# NixieClock_68k.net
KiCad netlist of a schematic drawn in EAGLE
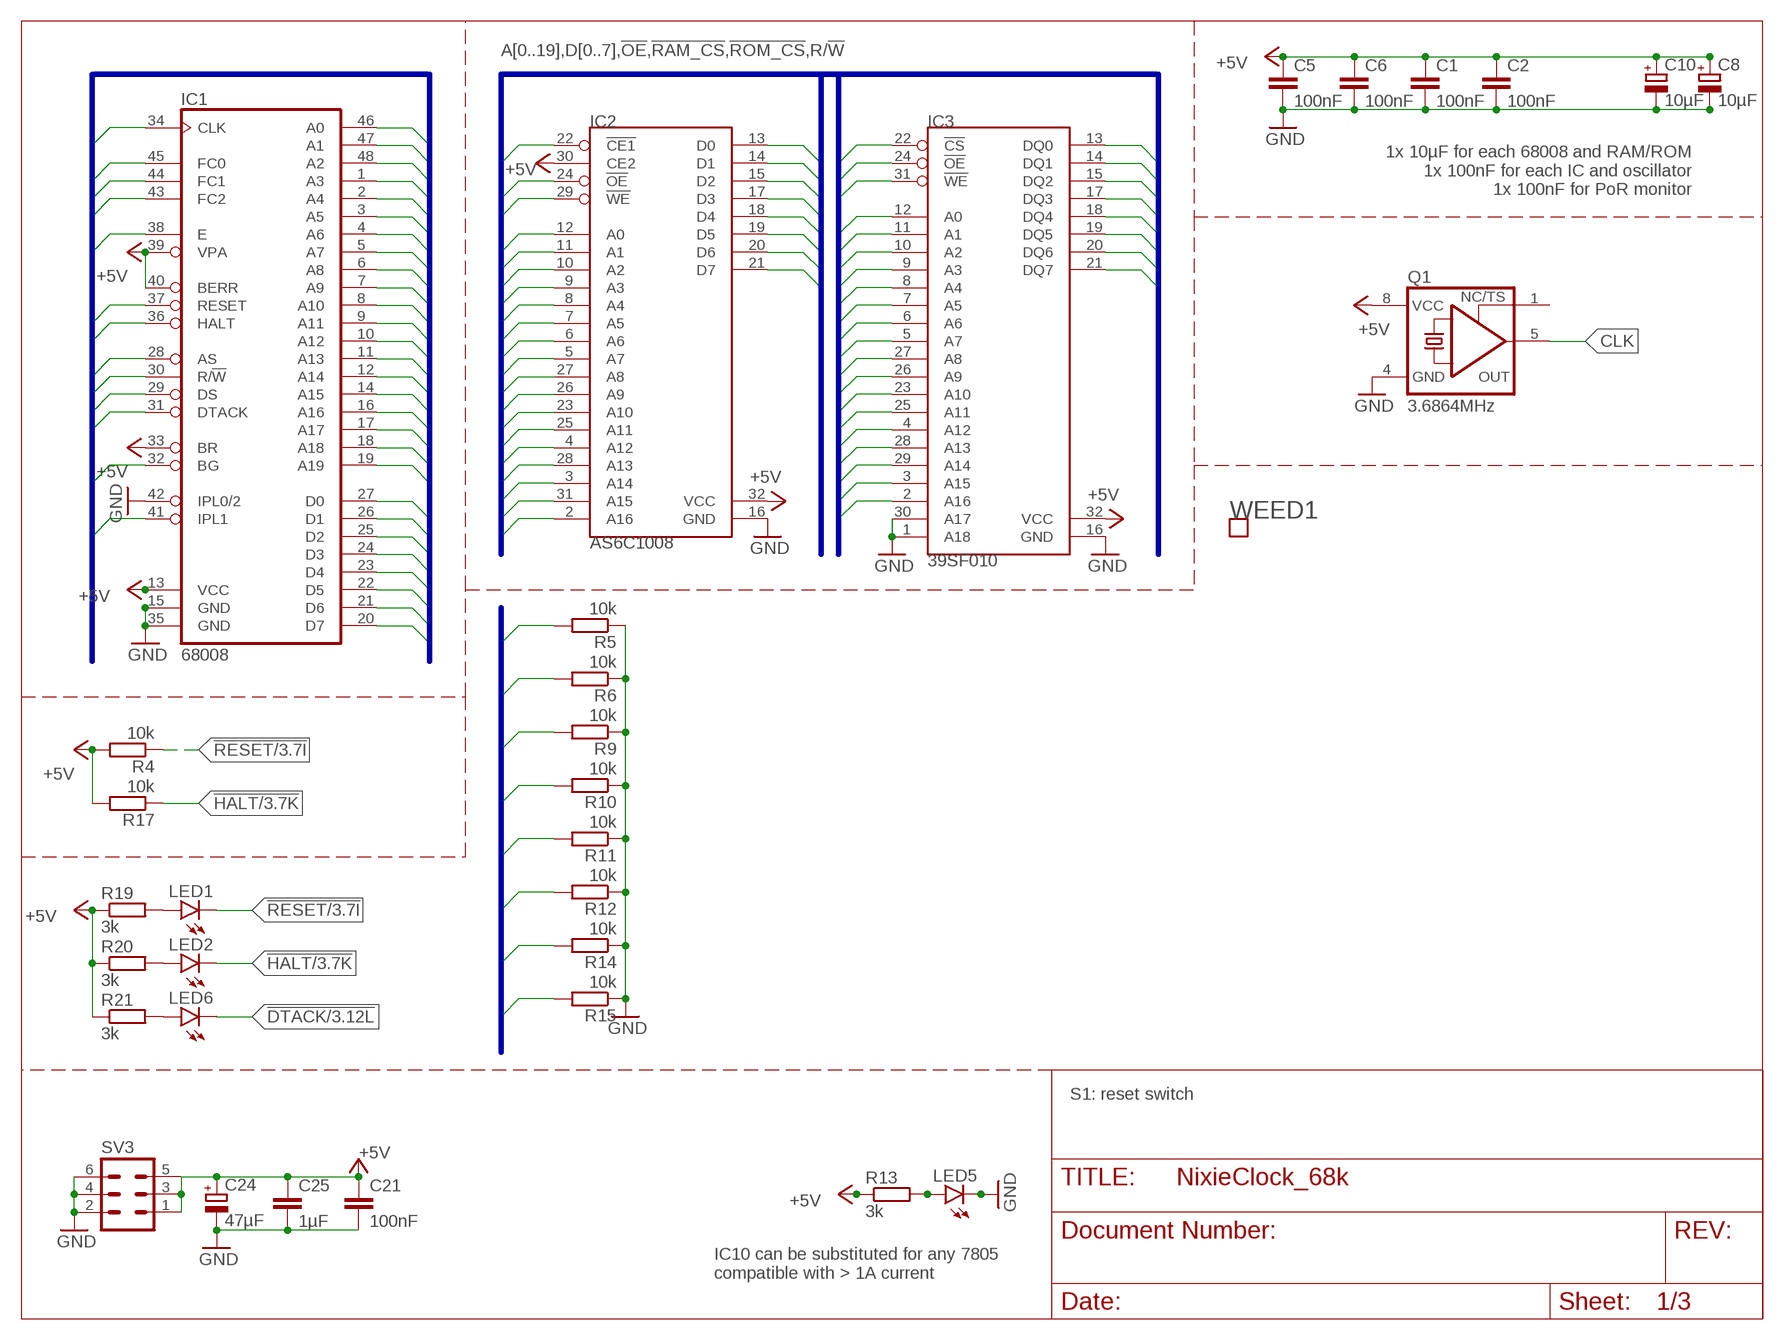
[diagram p0: schematic, sheet 1]
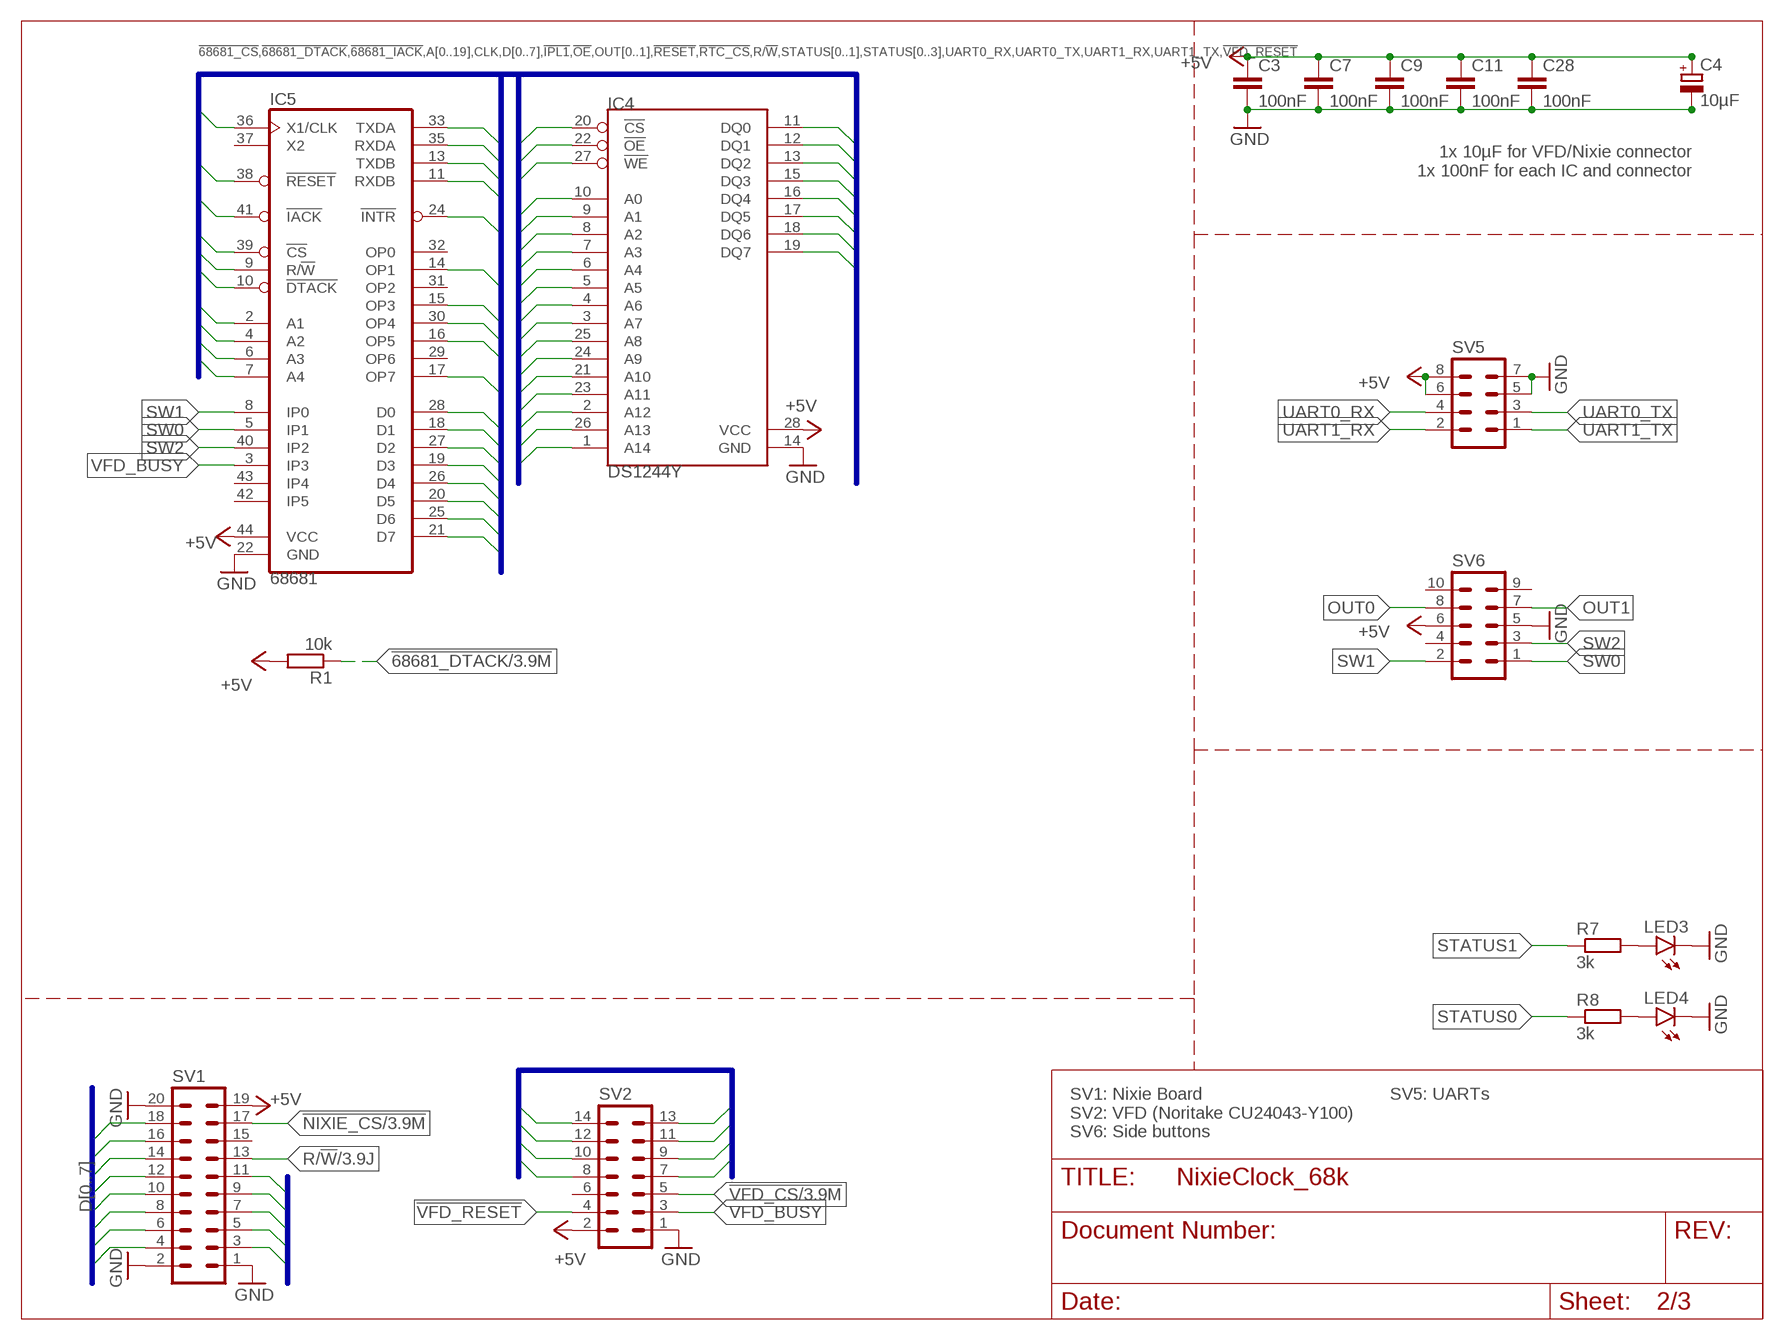
[diagram p1: schematic, sheet 2]
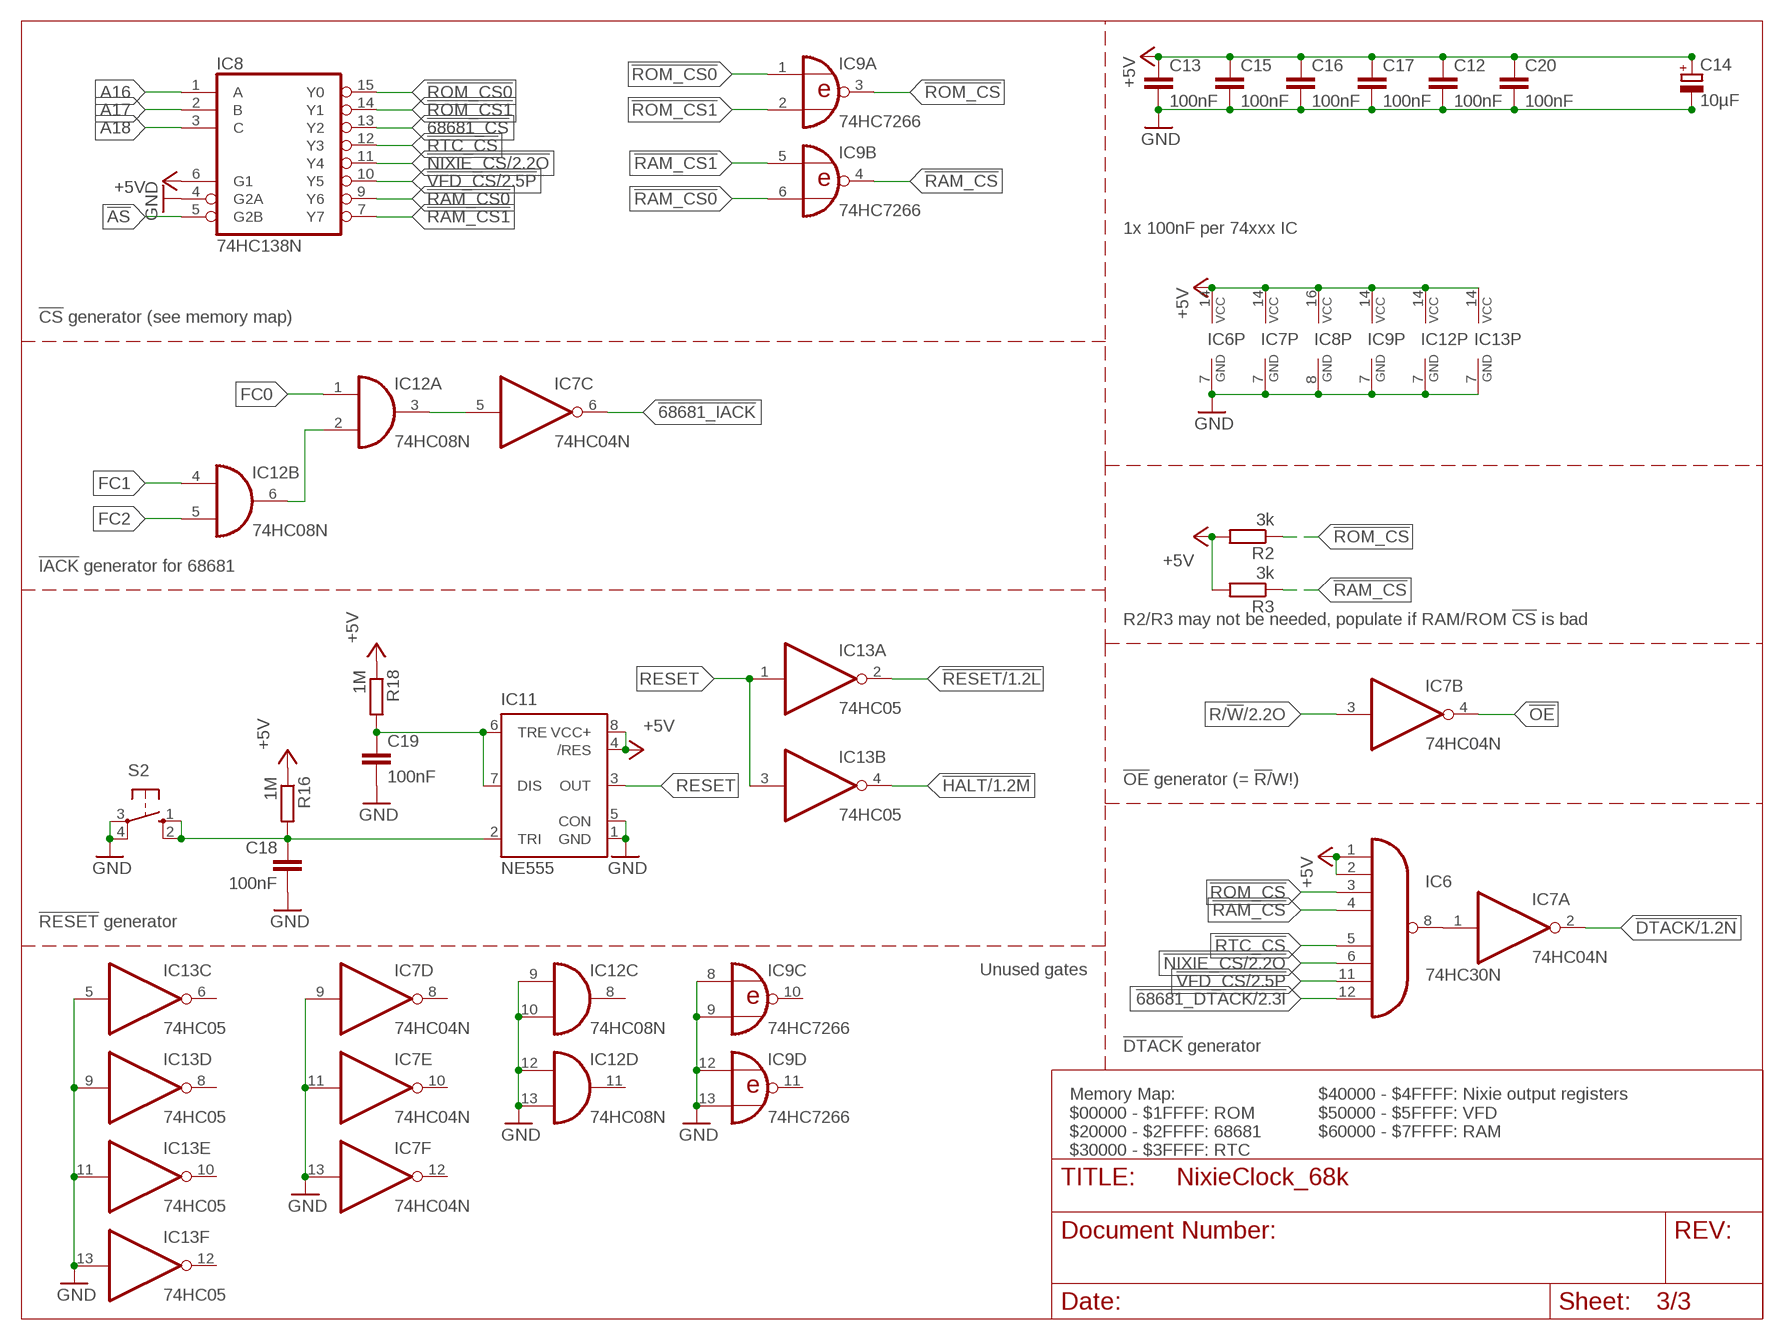
[diagram p2: schematic, sheet 3]

(export (version "E")
  (design (tool "Eeschema 10.0.6"))
  (components
    (comp (ref "C12")
      (value "100nF")
      (footprint "eagle-import:C0805")
      (libsource (lib "eagle-import") (part "C-EUC0805"))
    )
    (comp (ref "C13")
      (value "100nF")
      (footprint "eagle-import:C0805")
      (libsource (lib "eagle-import") (part "C-EUC0805"))
    )
    (comp (ref "C14")
      (value "10µF")
      (footprint "eagle-import:SMC_B")
      (libsource (lib "eagle-import") (part "CPOL-EUSMCB"))
    )
    (comp (ref "C15")
      (value "100nF")
      (footprint "eagle-import:C0805")
      (libsource (lib "eagle-import") (part "C-EUC0805"))
    )
    (comp (ref "C16")
      (value "100nF")
      (footprint "eagle-import:C0805")
      (libsource (lib "eagle-import") (part "C-EUC0805"))
    )
    (comp (ref "C17")
      (value "100nF")
      (footprint "eagle-import:C0805")
      (libsource (lib "eagle-import") (part "C-EUC0805"))
    )
    (comp (ref "C18")
      (value "100nF")
      (footprint "eagle-import:C0805")
      (libsource (lib "eagle-import") (part "C-EUC0805"))
    )
    (comp (ref "C19")
      (value "100nF")
      (footprint "eagle-import:C0805")
      (libsource (lib "eagle-import") (part "C-EUC0805"))
    )
    (comp (ref "C20")
      (value "100nF")
      (footprint "eagle-import:C0805")
      (libsource (lib "eagle-import") (part "C-EUC0805"))
    )
    (comp (ref "IC6")
      (value "74HC30N")
      (footprint "eagle-import:DIL14")
      (fields (field (name "MOUSER") "595-CD74HC30E"))
      (libsource (lib "eagle-import") (part "7430NHC"))
    )
    (comp (ref "IC7")
      (value "74HC04N")
      (footprint "eagle-import:DIL14")
      (fields (field (name "MOUSER") "595-SN74HC04AN"))
      (libsource (lib "eagle-import") (part "7404NHC"))
    )
    (comp (ref "IC8")
      (value "74HC138N")
      (footprint "eagle-import:DIL16")
      (fields (field (name "MOUSER") "595-SN74HC138N"))
      (libsource (lib "eagle-import") (part "74138NHC"))
    )
    (comp (ref "IC9")
      (value "74HC7266")
      (footprint "eagle-import:DIL14")
      (fields (field (name "MOUSER") "595-CD74HC7266E"))
      (libsource (lib "eagle-import") (part "74266NHC"))
    )
    (comp (ref "IC11")
      (value "NE555")
      (footprint "eagle-import:DIL-08")
      (fields (field (name "MF") "Arrow Electronics") (field (name "MPN") "NE555N"))
      (libsource (lib "eagle-import") (part "NE555"))
    )
    (comp (ref "IC12")
      (value "74HC08N")
      (footprint "eagle-import:DIL14")
      (fields (field (name "MOUSER") "595-SN74HC08AN"))
      (libsource (lib "eagle-import") (part "7408NHC"))
    )
    (comp (ref "IC13")
      (value "74HC05")
      (footprint "eagle-import:DIL14")
      (fields (field (name "MOUSER") "595-SN74HC05N"))
      (libsource (lib "eagle-import") (part "7405NHCT"))
    )
    (comp (ref "R2")
      (value "3k")
      (footprint "eagle-import:R2012")
      (libsource (lib "eagle-import") (part "R-EU_R2012"))
    )
    (comp (ref "R3")
      (value "3k")
      (footprint "eagle-import:R2012")
      (libsource (lib "eagle-import") (part "R-EU_R2012"))
    )
    (comp (ref "R16")
      (value "1M")
      (footprint "eagle-import:R2012")
      (libsource (lib "eagle-import") (part "R-EU_R2012"))
    )
    (comp (ref "R18")
      (value "1M")
      (footprint "eagle-import:R2012")
      (libsource (lib "eagle-import") (part "R-EU_R2012"))
    )
    (comp (ref "S2")
      (value "10-XX")
      (footprint "eagle-import:B3F-10XX")
      (fields (field (name "MPN") "B3F-1000"))
      (libsource (lib "eagle-import") (part "10-XX"))
    )
    (comp (ref "C3")
      (value "100nF")
      (footprint "eagle-import:C0805")
      (libsource (lib "eagle-import") (part "C-EUC0805"))
    )
    (comp (ref "C4")
      (value "10µF")
      (footprint "eagle-import:SMC_B")
      (libsource (lib "eagle-import") (part "CPOL-EUSMCB"))
    )
    (comp (ref "C7")
      (value "100nF")
      (footprint "eagle-import:C0805")
      (libsource (lib "eagle-import") (part "C-EUC0805"))
    )
    (comp (ref "C9")
      (value "100nF")
      (footprint "eagle-import:C0805")
      (libsource (lib "eagle-import") (part "C-EUC0805"))
    )
    (comp (ref "C11")
      (value "100nF")
      (footprint "eagle-import:C0805")
      (libsource (lib "eagle-import") (part "C-EUC0805"))
    )
    (comp (ref "C28")
      (value "100nF")
      (footprint "eagle-import:C0805")
      (libsource (lib "eagle-import") (part "C-EUC0805"))
    )
    (comp (ref "IC4")
      (value "DS1244Y")
      (footprint "eagle-import:DIL28-6")
      (libsource (lib "eagle-import") (part "DS1244EDIP-28"))
    )
    (comp (ref "IC5")
      (value "68681")
      (footprint "eagle-import:PLCC-S44")
      (libsource (lib "eagle-import") (part "MC68681PLCC44-SOCKET"))
    )
    (comp (ref "LED3")
      (value "LEDCHIPLED_1206")
      (footprint "eagle-import:CHIPLED_1206")
      (libsource (lib "eagle-import") (part "LEDCHIPLED_1206"))
    )
    (comp (ref "LED4")
      (value "LEDCHIPLED_1206")
      (footprint "eagle-import:CHIPLED_1206")
      (libsource (lib "eagle-import") (part "LEDCHIPLED_1206"))
    )
    (comp (ref "R1")
      (value "10k")
      (footprint "eagle-import:R2012")
      (libsource (lib "eagle-import") (part "R-EU_R2012"))
    )
    (comp (ref "R7")
      (value "3k")
      (footprint "eagle-import:R2012")
      (libsource (lib "eagle-import") (part "R-EU_R2012"))
    )
    (comp (ref "R8")
      (value "3k")
      (footprint "eagle-import:R2012")
      (libsource (lib "eagle-import") (part "R-EU_R2012"))
    )
    (comp (ref "SV1")
      (value "MA10-2")
      (footprint "eagle-import:MA10-2")
      (libsource (lib "eagle-import") (part "MA10-2"))
    )
    (comp (ref "SV2")
      (value "MA07-2")
      (footprint "eagle-import:MA07-2")
      (libsource (lib "eagle-import") (part "MA07-2"))
    )
    (comp (ref "SV5")
      (value "MA04-2")
      (footprint "eagle-import:MA04-2")
      (libsource (lib "eagle-import") (part "MA04-2"))
    )
    (comp (ref "SV6")
      (value "MA05-2")
      (footprint "eagle-import:MA05-2")
      (libsource (lib "eagle-import") (part "MA05-2"))
    )
    (comp (ref "C1")
      (value "100nF")
      (footprint "eagle-import:C0805")
      (libsource (lib "eagle-import") (part "C-EUC0805"))
    )
    (comp (ref "C2")
      (value "100nF")
      (footprint "eagle-import:C0805")
      (libsource (lib "eagle-import") (part "C-EUC0805"))
    )
    (comp (ref "C5")
      (value "100nF")
      (footprint "eagle-import:C0805")
      (libsource (lib "eagle-import") (part "C-EUC0805"))
    )
    (comp (ref "C6")
      (value "100nF")
      (footprint "eagle-import:C0805")
      (libsource (lib "eagle-import") (part "C-EUC0805"))
    )
    (comp (ref "C8")
      (value "10µF")
      (footprint "eagle-import:SMC_B")
      (libsource (lib "eagle-import") (part "CPOL-EUSMCB"))
    )
    (comp (ref "C10")
      (value "10µF")
      (footprint "eagle-import:SMC_B")
      (libsource (lib "eagle-import") (part "CPOL-EUSMCB"))
    )
    (comp (ref "C21")
      (value "100nF")
      (footprint "eagle-import:C0805")
      (libsource (lib "eagle-import") (part "C-EUC0805"))
    )
    (comp (ref "C24")
      (value "47µF")
      (footprint "eagle-import:CT6032")
      (libsource (lib "eagle-import") (part "CPOL-EUCT6032"))
    )
    (comp (ref "C25")
      (value "1µF")
      (footprint "eagle-import:C0805")
      (libsource (lib "eagle-import") (part "C-EUC0805"))
    )
    (comp (ref "IC1")
      (value "68008")
      (footprint "eagle-import:DIL48")
      (libsource (lib "eagle-import") (part "MC68008P"))
    )
    (comp (ref "IC2")
      (value "AS6C1008")
      (footprint "eagle-import:DIL32")
      (libsource (lib "eagle-import") (part "AS6C1008"))
    )
    (comp (ref "IC3")
      (value "39SF010")
      (footprint "eagle-import:DIL32")
      (fields (field (name "MOUSER") "804-39SF010A7CPHE"))
      (libsource (lib "eagle-import") (part "SST39SF0X0PDIP32"))
    )
    (comp (ref "LED1")
      (value "LEDCHIPLED_1206")
      (footprint "eagle-import:CHIPLED_1206")
      (libsource (lib "eagle-import") (part "LEDCHIPLED_1206"))
    )
    (comp (ref "LED2")
      (value "LEDCHIPLED_1206")
      (footprint "eagle-import:CHIPLED_1206")
      (libsource (lib "eagle-import") (part "LEDCHIPLED_1206"))
    )
    (comp (ref "LED5")
      (value "LEDCHIPLED_1206")
      (footprint "eagle-import:CHIPLED_1206")
      (libsource (lib "eagle-import") (part "LEDCHIPLED_1206"))
    )
    (comp (ref "LED6")
      (value "LEDCHIPLED_1206")
      (footprint "eagle-import:CHIPLED_1206")
      (libsource (lib "eagle-import") (part "LEDCHIPLED_1206"))
    )
    (comp (ref "Q1")
      (value "3.6864MHz")
      (footprint "eagle-import:DIL08S")
      (libsource (lib "eagle-import") (part "XO-8"))
    )
    (comp (ref "R4")
      (value "10k")
      (footprint "eagle-import:R2012")
      (libsource (lib "eagle-import") (part "R-EU_R2012"))
    )
    (comp (ref "R5")
      (value "10k")
      (footprint "eagle-import:R2012")
      (libsource (lib "eagle-import") (part "R-EU_R2012"))
    )
    (comp (ref "R6")
      (value "10k")
      (footprint "eagle-import:R2012")
      (libsource (lib "eagle-import") (part "R-EU_R2012"))
    )
    (comp (ref "R9")
      (value "10k")
      (footprint "eagle-import:R2012")
      (libsource (lib "eagle-import") (part "R-EU_R2012"))
    )
    (comp (ref "R10")
      (value "10k")
      (footprint "eagle-import:R2012")
      (libsource (lib "eagle-import") (part "R-EU_R2012"))
    )
    (comp (ref "R11")
      (value "10k")
      (footprint "eagle-import:R2012")
      (libsource (lib "eagle-import") (part "R-EU_R2012"))
    )
    (comp (ref "R12")
      (value "10k")
      (footprint "eagle-import:R2012")
      (libsource (lib "eagle-import") (part "R-EU_R2012"))
    )
    (comp (ref "R13")
      (value "3k")
      (footprint "eagle-import:R2012")
      (libsource (lib "eagle-import") (part "R-EU_R2012"))
    )
    (comp (ref "R14")
      (value "10k")
      (footprint "eagle-import:R2012")
      (libsource (lib "eagle-import") (part "R-EU_R2012"))
    )
    (comp (ref "R15")
      (value "10k")
      (footprint "eagle-import:R2012")
      (libsource (lib "eagle-import") (part "R-EU_R2012"))
    )
    (comp (ref "R17")
      (value "10k")
      (footprint "eagle-import:R2012")
      (libsource (lib "eagle-import") (part "R-EU_R2012"))
    )
    (comp (ref "R19")
      (value "3k")
      (footprint "eagle-import:R2012")
      (libsource (lib "eagle-import") (part "R-EU_R2012"))
    )
    (comp (ref "R20")
      (value "3k")
      (footprint "eagle-import:R2012")
      (libsource (lib "eagle-import") (part "R-EU_R2012"))
    )
    (comp (ref "R21")
      (value "3k")
      (footprint "eagle-import:R2012")
      (libsource (lib "eagle-import") (part "R-EU_R2012"))
    )
    (comp (ref "SV3")
      (value "MA03-2")
      (footprint "eagle-import:MA03-2")
      (libsource (lib "eagle-import") (part "MA03-2"))
    )
    (comp (ref "WEED1")
      (value "WEED")
      (footprint "eagle-import:DOINK")
      (libsource (lib "eagle-import") (part "WEED"))
    )
  )
  (nets
    (net (code "1") (name "+5V") (class "Default")
      (node (ref "C1") (pin "1") (pinfunction "1_1") (pintype "passive"))
      (node (ref "C10") (pin "+") (pinfunction "+_+") (pintype "passive"))
      (node (ref "C11") (pin "1") (pinfunction "1_1") (pintype "passive"))
      (node (ref "C12") (pin "1") (pinfunction "1_1") (pintype "passive"))
      (node (ref "C13") (pin "1") (pinfunction "1_1") (pintype "passive"))
      (node (ref "C14") (pin "+") (pinfunction "+_+") (pintype "passive"))
      (node (ref "C15") (pin "1") (pinfunction "1_1") (pintype "passive"))
      (node (ref "C16") (pin "1") (pinfunction "1_1") (pintype "passive"))
      (node (ref "C17") (pin "1") (pinfunction "1_1") (pintype "passive"))
      (node (ref "C2") (pin "1") (pinfunction "1_1") (pintype "passive"))
      (node (ref "C20") (pin "1") (pinfunction "1_1") (pintype "passive"))
      (node (ref "C21") (pin "1") (pinfunction "1_1") (pintype "passive"))
      (node (ref "C24") (pin "+") (pinfunction "+_+") (pintype "passive"))
      (node (ref "C25") (pin "1") (pinfunction "1_1") (pintype "passive"))
      (node (ref "C28") (pin "1") (pinfunction "1_1") (pintype "passive"))
      (node (ref "C3") (pin "1") (pinfunction "1_1") (pintype "passive"))
      (node (ref "C4") (pin "+") (pinfunction "+_+") (pintype "passive"))
      (node (ref "C5") (pin "1") (pinfunction "1_1") (pintype "passive"))
      (node (ref "C6") (pin "1") (pinfunction "1_1") (pintype "passive"))
      (node (ref "C7") (pin "1") (pinfunction "1_1") (pintype "passive"))
      (node (ref "C8") (pin "+") (pinfunction "+_+") (pintype "passive"))
      (node (ref "C9") (pin "1") (pinfunction "1_1") (pintype "passive"))
      (node (ref "IC1") (pin "13") (pinfunction "VCC_13") (pintype "power_in"))
      (node (ref "IC1") (pin "33") (pinfunction "BR_33") (pintype "input"))
      (node (ref "IC1") (pin "39") (pinfunction "VPA_39") (pintype "input"))
      (node (ref "IC1") (pin "40") (pinfunction "BERR_40") (pintype "input"))
      (node (ref "IC11") (pin "4") (pinfunction "/RES_4") (pintype "input"))
      (node (ref "IC11") (pin "8") (pinfunction "VCC+_8") (pintype "power_in"))
      (node (ref "IC12") (pin "14") (pinfunction "VCC_14") (pintype "power_in"))
      (node (ref "IC13") (pin "14") (pinfunction "VCC_14") (pintype "power_in"))
      (node (ref "IC2") (pin "30") (pinfunction "CE2_30") (pintype "input"))
      (node (ref "IC2") (pin "32") (pinfunction "VCC_32") (pintype "power_in"))
      (node (ref "IC3") (pin "32") (pinfunction "VCC_32") (pintype "power_in"))
      (node (ref "IC4") (pin "28") (pinfunction "VCC_28") (pintype "power_in"))
      (node (ref "IC5") (pin "44") (pinfunction "VCC_44") (pintype "power_in"))
      (node (ref "IC6") (pin "1") (pinfunction "I0_1") (pintype "input"))
      (node (ref "IC6") (pin "14") (pinfunction "VCC_14") (pintype "power_in"))
      (node (ref "IC6") (pin "2") (pinfunction "I1_2") (pintype "input"))
      (node (ref "IC7") (pin "14") (pinfunction "VCC_14") (pintype "power_in"))
      (node (ref "IC8") (pin "16") (pinfunction "VCC_16") (pintype "power_in"))
      (node (ref "IC8") (pin "6") (pinfunction "G1_6") (pintype "input"))
      (node (ref "IC9") (pin "14") (pinfunction "VCC_14") (pintype "power_in"))
      (node (ref "Q1") (pin "8") (pinfunction "VCC_8") (pintype "power_in"))
      (node (ref "R1") (pin "2") (pinfunction "2_2") (pintype "passive"))
      (node (ref "R13") (pin "1") (pinfunction "1_1") (pintype "passive"))
      (node (ref "R16") (pin "1") (pinfunction "1_1") (pintype "passive"))
      (node (ref "R17") (pin "2") (pinfunction "2_2") (pintype "passive"))
      (node (ref "R18") (pin "1") (pinfunction "1_1") (pintype "passive"))
      (node (ref "R19") (pin "1") (pinfunction "1_1") (pintype "passive"))
      (node (ref "R2") (pin "2") (pinfunction "2_2") (pintype "passive"))
      (node (ref "R20") (pin "1") (pinfunction "1_1") (pintype "passive"))
      (node (ref "R21") (pin "1") (pinfunction "1_1") (pintype "passive"))
      (node (ref "R3") (pin "2") (pinfunction "2_2") (pintype "passive"))
      (node (ref "R4") (pin "2") (pinfunction "2_2") (pintype "passive"))
      (node (ref "SV1") (pin "19") (pinfunction "19_19") (pintype "passive"))
      (node (ref "SV2") (pin "2") (pinfunction "2_2") (pintype "passive"))
      (node (ref "SV3") (pin "1") (pinfunction "1_1") (pintype "passive"))
      (node (ref "SV3") (pin "3") (pinfunction "3_3") (pintype "passive"))
      (node (ref "SV3") (pin "5") (pinfunction "5_5") (pintype "passive"))
      (node (ref "SV5") (pin "6") (pinfunction "6_6") (pintype "passive"))
      (node (ref "SV5") (pin "8") (pinfunction "8_8") (pintype "passive"))
      (node (ref "SV6") (pin "6") (pinfunction "6_6") (pintype "passive"))
    )
    (net (code "5") (name "A0") (class "Default")
      (node (ref "IC1") (pin "46") (pinfunction "A0_46") (pintype "output"))
      (node (ref "IC2") (pin "12") (pinfunction "A0_12") (pintype "input"))
      (node (ref "IC3") (pin "12") (pinfunction "A0_12") (pintype "input"))
      (node (ref "IC4") (pin "10") (pinfunction "A0_10") (pintype "input"))
      (node (ref "IC5") (pin "2") (pinfunction "A1_2") (pintype "input"))
      (node (ref "SV1") (pin "3") (pinfunction "3_3") (pintype "passive"))
    )
    (net (code "6") (name "A1") (class "Default")
      (node (ref "IC1") (pin "47") (pinfunction "A1_47") (pintype "output"))
      (node (ref "IC2") (pin "11") (pinfunction "A1_11") (pintype "input"))
      (node (ref "IC3") (pin "11") (pinfunction "A1_11") (pintype "input"))
      (node (ref "IC4") (pin "9") (pinfunction "A1_9") (pintype "input"))
      (node (ref "IC5") (pin "4") (pinfunction "A2_4") (pintype "input"))
      (node (ref "SV1") (pin "5") (pinfunction "5_5") (pintype "passive"))
    )
    (net (code "7") (name "A2") (class "Default")
      (node (ref "IC1") (pin "48") (pinfunction "A2_48") (pintype "output"))
      (node (ref "IC2") (pin "10") (pinfunction "A2_10") (pintype "input"))
      (node (ref "IC3") (pin "10") (pinfunction "A2_10") (pintype "input"))
      (node (ref "IC4") (pin "8") (pinfunction "A2_8") (pintype "input"))
      (node (ref "IC5") (pin "6") (pinfunction "A3_6") (pintype "input"))
      (node (ref "SV1") (pin "7") (pinfunction "7_7") (pintype "passive"))
    )
    (net (code "8") (name "A3") (class "Default")
      (node (ref "IC1") (pin "1") (pinfunction "A3_1") (pintype "output"))
      (node (ref "IC2") (pin "9") (pinfunction "A3_9") (pintype "input"))
      (node (ref "IC3") (pin "9") (pinfunction "A3_9") (pintype "input"))
      (node (ref "IC4") (pin "7") (pinfunction "A3_7") (pintype "input"))
      (node (ref "IC5") (pin "7") (pinfunction "A4_7") (pintype "input"))
      (node (ref "SV1") (pin "9") (pinfunction "9_9") (pintype "passive"))
    )
    (net (code "9") (name "A4") (class "Default")
      (node (ref "IC1") (pin "2") (pinfunction "A4_2") (pintype "output"))
      (node (ref "IC2") (pin "8") (pinfunction "A4_8") (pintype "input"))
      (node (ref "IC3") (pin "8") (pinfunction "A4_8") (pintype "input"))
      (node (ref "IC4") (pin "6") (pinfunction "A4_6") (pintype "input"))
      (node (ref "SV1") (pin "11") (pinfunction "11_11") (pintype "passive"))
    )
    (net (code "10") (name "A5") (class "Default")
      (node (ref "IC1") (pin "3") (pinfunction "A5_3") (pintype "output"))
      (node (ref "IC2") (pin "7") (pinfunction "A5_7") (pintype "input"))
      (node (ref "IC3") (pin "7") (pinfunction "A5_7") (pintype "input"))
      (node (ref "IC4") (pin "5") (pinfunction "A5_5") (pintype "input"))
    )
    (net (code "11") (name "A6") (class "Default")
      (node (ref "IC1") (pin "4") (pinfunction "A6_4") (pintype "output"))
      (node (ref "IC2") (pin "6") (pinfunction "A6_6") (pintype "input"))
      (node (ref "IC3") (pin "6") (pinfunction "A6_6") (pintype "input"))
      (node (ref "IC4") (pin "4") (pinfunction "A6_4") (pintype "input"))
    )
    (net (code "12") (name "A7") (class "Default")
      (node (ref "IC1") (pin "5") (pinfunction "A7_5") (pintype "output"))
      (node (ref "IC2") (pin "5") (pinfunction "A7_5") (pintype "input"))
      (node (ref "IC3") (pin "5") (pinfunction "A7_5") (pintype "input"))
      (node (ref "IC4") (pin "3") (pinfunction "A7_3") (pintype "input"))
    )
    (net (code "13") (name "A8") (class "Default")
      (node (ref "IC1") (pin "6") (pinfunction "A8_6") (pintype "output"))
      (node (ref "IC2") (pin "27") (pinfunction "A8_27") (pintype "input"))
      (node (ref "IC3") (pin "27") (pinfunction "A8_27") (pintype "input"))
      (node (ref "IC4") (pin "25") (pinfunction "A8_25") (pintype "input"))
    )
    (net (code "14") (name "A9") (class "Default")
      (node (ref "IC1") (pin "7") (pinfunction "A9_7") (pintype "output"))
      (node (ref "IC2") (pin "26") (pinfunction "A9_26") (pintype "input"))
      (node (ref "IC3") (pin "26") (pinfunction "A9_26") (pintype "input"))
      (node (ref "IC4") (pin "24") (pinfunction "A9_24") (pintype "input"))
    )
    (net (code "15") (name "A10") (class "Default")
      (node (ref "IC1") (pin "8") (pinfunction "A10_8") (pintype "output"))
      (node (ref "IC2") (pin "23") (pinfunction "A10_23") (pintype "input"))
      (node (ref "IC3") (pin "23") (pinfunction "A10_23") (pintype "input"))
      (node (ref "IC4") (pin "21") (pinfunction "A10_21") (pintype "input"))
    )
    (net (code "16") (name "A11") (class "Default")
      (node (ref "IC1") (pin "9") (pinfunction "A11_9") (pintype "output"))
      (node (ref "IC2") (pin "25") (pinfunction "A11_25") (pintype "input"))
      (node (ref "IC3") (pin "25") (pinfunction "A11_25") (pintype "input"))
      (node (ref "IC4") (pin "23") (pinfunction "A11_23") (pintype "input"))
    )
    (net (code "17") (name "A12") (class "Default")
      (node (ref "IC1") (pin "10") (pinfunction "A12_10") (pintype "output"))
      (node (ref "IC2") (pin "4") (pinfunction "A12_4") (pintype "input"))
      (node (ref "IC3") (pin "4") (pinfunction "A12_4") (pintype "input"))
      (node (ref "IC4") (pin "2") (pinfunction "A12_2") (pintype "input"))
    )
    (net (code "18") (name "A13") (class "Default")
      (node (ref "IC1") (pin "11") (pinfunction "A13_11") (pintype "output"))
      (node (ref "IC2") (pin "28") (pinfunction "A13_28") (pintype "input"))
      (node (ref "IC3") (pin "28") (pinfunction "A13_28") (pintype "input"))
      (node (ref "IC4") (pin "26") (pinfunction "A13_26") (pintype "input"))
    )
    (net (code "19") (name "A14") (class "Default")
      (node (ref "IC1") (pin "12") (pinfunction "A14_12") (pintype "output"))
      (node (ref "IC2") (pin "3") (pinfunction "A14_3") (pintype "input"))
      (node (ref "IC3") (pin "29") (pinfunction "A14_29") (pintype "input"))
      (node (ref "IC4") (pin "1") (pinfunction "A14_1") (pintype "input"))
    )
    (net (code "20") (name "A15") (class "Default")
      (node (ref "IC1") (pin "14") (pinfunction "A15_14") (pintype "output"))
      (node (ref "IC2") (pin "31") (pinfunction "A15_31") (pintype "input"))
      (node (ref "IC3") (pin "3") (pinfunction "A15_3") (pintype "input"))
    )
    (net (code "21") (name "A16") (class "Default")
      (node (ref "IC1") (pin "16") (pinfunction "A16_16") (pintype "output"))
      (node (ref "IC2") (pin "2") (pinfunction "A16_2") (pintype "input"))
      (node (ref "IC3") (pin "2") (pinfunction "A16_2") (pintype "input"))
      (node (ref "IC8") (pin "1") (pinfunction "A_1") (pintype "input"))
    )
    (net (code "22") (name "A17") (class "Default")
      (node (ref "IC1") (pin "17") (pinfunction "A17_17") (pintype "output"))
      (node (ref "IC8") (pin "2") (pinfunction "B_2") (pintype "input"))
    )
    (net (code "23") (name "A18") (class "Default")
      (node (ref "IC1") (pin "18") (pinfunction "A18_18") (pintype "output"))
      (node (ref "IC8") (pin "3") (pinfunction "C_3") (pintype "input"))
    )
    (net (code "24") (name "CLK") (class "Default")
      (node (ref "IC1") (pin "34") (pinfunction "CLK_34") (pintype "input"))
      (node (ref "IC5") (pin "36") (pinfunction "X1/CLK_36") (pintype "input"))
      (node (ref "Q1") (pin "5") (pinfunction "OUT_5") (pintype "output"))
    )
    (net (code "25") (name "D0") (class "Default")
      (node (ref "IC1") (pin "27") (pinfunction "D0_27") (pintype "bidirectional"))
      (node (ref "IC2") (pin "13") (pinfunction "D0_13") (pintype "bidirectional"))
      (node (ref "IC3") (pin "13") (pinfunction "DQ0_13") (pintype "bidirectional"))
      (node (ref "IC4") (pin "11") (pinfunction "DQ0_11") (pintype "bidirectional"))
      (node (ref "IC5") (pin "28") (pinfunction "D0_28") (pintype "bidirectional"))
      (node (ref "R5") (pin "2") (pinfunction "2_2") (pintype "passive"))
      (node (ref "SV1") (pin "8") (pinfunction "8_8") (pintype "passive"))
      (node (ref "SV2") (pin "7") (pinfunction "7_7") (pintype "passive"))
    )
    (net (code "26") (name "D1") (class "Default")
      (node (ref "IC1") (pin "26") (pinfunction "D1_26") (pintype "bidirectional"))
      (node (ref "IC2") (pin "14") (pinfunction "D1_14") (pintype "bidirectional"))
      (node (ref "IC3") (pin "14") (pinfunction "DQ1_14") (pintype "bidirectional"))
      (node (ref "IC4") (pin "12") (pinfunction "DQ1_12") (pintype "bidirectional"))
      (node (ref "IC5") (pin "18") (pinfunction "D1_18") (pintype "bidirectional"))
      (node (ref "R6") (pin "2") (pinfunction "2_2") (pintype "passive"))
      (node (ref "SV1") (pin "6") (pinfunction "6_6") (pintype "passive"))
      (node (ref "SV2") (pin "8") (pinfunction "8_8") (pintype "passive"))
    )
    (net (code "27") (name "D2") (class "Default")
      (node (ref "IC1") (pin "25") (pinfunction "D2_25") (pintype "bidirectional"))
      (node (ref "IC2") (pin "15") (pinfunction "D2_15") (pintype "bidirectional"))
      (node (ref "IC3") (pin "15") (pinfunction "DQ2_15") (pintype "bidirectional"))
      (node (ref "IC4") (pin "13") (pinfunction "DQ2_13") (pintype "bidirectional"))
      (node (ref "IC5") (pin "27") (pinfunction "D2_27") (pintype "bidirectional"))
      (node (ref "R9") (pin "2") (pinfunction "2_2") (pintype "passive"))
      (node (ref "SV1") (pin "4") (pinfunction "4_4") (pintype "passive"))
      (node (ref "SV2") (pin "9") (pinfunction "9_9") (pintype "passive"))
    )
    (net (code "28") (name "D3") (class "Default")
      (node (ref "IC1") (pin "24") (pinfunction "D3_24") (pintype "bidirectional"))
      (node (ref "IC2") (pin "17") (pinfunction "D3_17") (pintype "bidirectional"))
      (node (ref "IC3") (pin "17") (pinfunction "DQ3_17") (pintype "bidirectional"))
      (node (ref "IC4") (pin "15") (pinfunction "DQ3_15") (pintype "bidirectional"))
      (node (ref "IC5") (pin "19") (pinfunction "D3_19") (pintype "bidirectional"))
      (node (ref "R10") (pin "2") (pinfunction "2_2") (pintype "passive"))
      (node (ref "SV1") (pin "10") (pinfunction "10_10") (pintype "passive"))
      (node (ref "SV2") (pin "10") (pinfunction "10_10") (pintype "passive"))
    )
    (net (code "29") (name "D4") (class "Default")
      (node (ref "IC1") (pin "23") (pinfunction "D4_23") (pintype "bidirectional"))
      (node (ref "IC2") (pin "18") (pinfunction "D4_18") (pintype "bidirectional"))
      (node (ref "IC3") (pin "18") (pinfunction "DQ4_18") (pintype "bidirectional"))
      (node (ref "IC4") (pin "16") (pinfunction "DQ4_16") (pintype "bidirectional"))
      (node (ref "IC5") (pin "26") (pinfunction "D4_26") (pintype "bidirectional"))
      (node (ref "R11") (pin "2") (pinfunction "2_2") (pintype "passive"))
      (node (ref "SV1") (pin "12") (pinfunction "12_12") (pintype "passive"))
      (node (ref "SV2") (pin "11") (pinfunction "11_11") (pintype "passive"))
    )
    (net (code "30") (name "D5") (class "Default")
      (node (ref "IC1") (pin "22") (pinfunction "D5_22") (pintype "bidirectional"))
      (node (ref "IC2") (pin "19") (pinfunction "D5_19") (pintype "bidirectional"))
      (node (ref "IC3") (pin "19") (pinfunction "DQ5_19") (pintype "bidirectional"))
      (node (ref "IC4") (pin "17") (pinfunction "DQ5_17") (pintype "bidirectional"))
      (node (ref "IC5") (pin "20") (pinfunction "D5_20") (pintype "bidirectional"))
      (node (ref "R12") (pin "2") (pinfunction "2_2") (pintype "passive"))
      (node (ref "SV1") (pin "14") (pinfunction "14_14") (pintype "passive"))
      (node (ref "SV2") (pin "12") (pinfunction "12_12") (pintype "passive"))
    )
    (net (code "31") (name "D6") (class "Default")
      (node (ref "IC1") (pin "21") (pinfunction "D6_21") (pintype "bidirectional"))
      (node (ref "IC2") (pin "20") (pinfunction "D6_20") (pintype "bidirectional"))
      (node (ref "IC3") (pin "20") (pinfunction "DQ6_20") (pintype "bidirectional"))
      (node (ref "IC4") (pin "18") (pinfunction "DQ6_18") (pintype "bidirectional"))
      (node (ref "IC5") (pin "25") (pinfunction "D6_25") (pintype "bidirectional"))
      (node (ref "R14") (pin "2") (pinfunction "2_2") (pintype "passive"))
      (node (ref "SV1") (pin "16") (pinfunction "16_16") (pintype "passive"))
      (node (ref "SV2") (pin "13") (pinfunction "13_13") (pintype "passive"))
    )
    (net (code "32") (name "D7") (class "Default")
      (node (ref "IC1") (pin "20") (pinfunction "D7_20") (pintype "bidirectional"))
      (node (ref "IC2") (pin "21") (pinfunction "D7_21") (pintype "bidirectional"))
      (node (ref "IC3") (pin "21") (pinfunction "DQ7_21") (pintype "bidirectional"))
      (node (ref "IC4") (pin "19") (pinfunction "DQ7_19") (pintype "bidirectional"))
      (node (ref "IC5") (pin "21") (pinfunction "D7_21") (pintype "bidirectional"))
      (node (ref "R15") (pin "2") (pinfunction "2_2") (pintype "passive"))
      (node (ref "SV1") (pin "18") (pinfunction "18_18") (pintype "passive"))
      (node (ref "SV2") (pin "14") (pinfunction "14_14") (pintype "passive"))
    )
    (net (code "33") (name "FC0") (class "Default")
      (node (ref "IC1") (pin "45") (pinfunction "FC0_45") (pintype "output"))
      (node (ref "IC12") (pin "1") (pinfunction "I0_1") (pintype "input"))
    )
    (net (code "34") (name "FC1") (class "Default")
      (node (ref "IC1") (pin "44") (pinfunction "FC1_44") (pintype "output"))
      (node (ref "IC12") (pin "4") (pinfunction "I0_4") (pintype "input"))
    )
    (net (code "35") (name "FC2") (class "Default")
      (node (ref "IC1") (pin "43") (pinfunction "FC2_43") (pintype "output"))
      (node (ref "IC12") (pin "5") (pinfunction "I1_5") (pintype "input"))
    )
    (net (code "36") (name "GND") (class "Default")
      (node (ref "C1") (pin "2") (pinfunction "2_2") (pintype "passive"))
      (node (ref "C10") (pin "-") (pinfunction "-_-") (pintype "passive"))
      (node (ref "C11") (pin "2") (pinfunction "2_2") (pintype "passive"))
      (node (ref "C12") (pin "2") (pinfunction "2_2") (pintype "passive"))
      (node (ref "C13") (pin "2") (pinfunction "2_2") (pintype "passive"))
      (node (ref "C14") (pin "-") (pinfunction "-_-") (pintype "passive"))
      (node (ref "C15") (pin "2") (pinfunction "2_2") (pintype "passive"))
      (node (ref "C16") (pin "2") (pinfunction "2_2") (pintype "passive"))
      (node (ref "C17") (pin "2") (pinfunction "2_2") (pintype "passive"))
      (node (ref "C18") (pin "2") (pinfunction "2_2") (pintype "passive"))
      (node (ref "C19") (pin "2") (pinfunction "2_2") (pintype "passive"))
      (node (ref "C2") (pin "2") (pinfunction "2_2") (pintype "passive"))
      (node (ref "C20") (pin "2") (pinfunction "2_2") (pintype "passive"))
      (node (ref "C21") (pin "2") (pinfunction "2_2") (pintype "passive"))
      (node (ref "C24") (pin "-") (pinfunction "-_-") (pintype "passive"))
      (node (ref "C25") (pin "2") (pinfunction "2_2") (pintype "passive"))
      (node (ref "C28") (pin "2") (pinfunction "2_2") (pintype "passive"))
      (node (ref "C3") (pin "2") (pinfunction "2_2") (pintype "passive"))
      (node (ref "C4") (pin "-") (pinfunction "-_-") (pintype "passive"))
      (node (ref "C5") (pin "2") (pinfunction "2_2") (pintype "passive"))
      (node (ref "C6") (pin "2") (pinfunction "2_2") (pintype "passive"))
      (node (ref "C7") (pin "2") (pinfunction "2_2") (pintype "passive"))
      (node (ref "C8") (pin "-") (pinfunction "-_-") (pintype "passive"))
      (node (ref "C9") (pin "2") (pinfunction "2_2") (pintype "passive"))
      (node (ref "IC1") (pin "15") (pinfunction "GND_15") (pintype "power_in"))
      (node (ref "IC1") (pin "35") (pinfunction "GND_35") (pintype "power_in"))
      (node (ref "IC1") (pin "42") (pinfunction "IPL0/2_42") (pintype "input"))
      (node (ref "IC11") (pin "1") (pinfunction "GND_1") (pintype "power_in"))
      (node (ref "IC11") (pin "5") (pinfunction "CON_5") (pintype "input"))
      (node (ref "IC12") (pin "10") (pinfunction "I1_10") (pintype "input"))
      (node (ref "IC12") (pin "12") (pinfunction "I0_12") (pintype "input"))
      (node (ref "IC12") (pin "13") (pinfunction "I1_13") (pintype "input"))
      (node (ref "IC12") (pin "7") (pinfunction "GND_7") (pintype "power_in"))
      (node (ref "IC12") (pin "9") (pinfunction "I0_9") (pintype "input"))
      (node (ref "IC13") (pin "11") (pinfunction "I_11") (pintype "input"))
      (node (ref "IC13") (pin "13") (pinfunction "I_13") (pintype "input"))
      (node (ref "IC13") (pin "5") (pinfunction "I_5") (pintype "input"))
      (node (ref "IC13") (pin "7") (pinfunction "GND_7") (pintype "power_in"))
      (node (ref "IC13") (pin "9") (pinfunction "I_9") (pintype "input"))
      (node (ref "IC2") (pin "16") (pinfunction "GND_16") (pintype "power_in"))
      (node (ref "IC3") (pin "1") (pinfunction "A18_1") (pintype "input"))
      (node (ref "IC3") (pin "16") (pinfunction "GND_16") (pintype "power_in"))
      (node (ref "IC3") (pin "30") (pinfunction "A17_30") (pintype "input"))
      (node (ref "IC4") (pin "14") (pinfunction "GND_14") (pintype "power_in"))
      (node (ref "IC5") (pin "22") (pinfunction "GND_22") (pintype "power_in"))
      (node (ref "IC6") (pin "7") (pinfunction "GND_7") (pintype "power_in"))
      (node (ref "IC7") (pin "11") (pinfunction "I_11") (pintype "input"))
      (node (ref "IC7") (pin "13") (pinfunction "I_13") (pintype "input"))
      (node (ref "IC7") (pin "7") (pinfunction "GND_7") (pintype "power_in"))
      (node (ref "IC7") (pin "9") (pinfunction "I_9") (pintype "input"))
      (node (ref "IC8") (pin "4") (pinfunction "G2A_4") (pintype "input"))
      (node (ref "IC8") (pin "8") (pinfunction "GND_8") (pintype "power_in"))
      (node (ref "IC9") (pin "12") (pinfunction "I0_12") (pintype "input"))
      (node (ref "IC9") (pin "13") (pinfunction "I1_13") (pintype "input"))
      (node (ref "IC9") (pin "7") (pinfunction "GND_7") (pintype "power_in"))
      (node (ref "IC9") (pin "8") (pinfunction "I0_8") (pintype "input"))
      (node (ref "IC9") (pin "9") (pinfunction "I1_9") (pintype "input"))
      (node (ref "LED3") (pin "C") (pinfunction "C_C") (pintype "passive"))
      (node (ref "LED4") (pin "C") (pinfunction "C_C") (pintype "passive"))
      (node (ref "LED5") (pin "C") (pinfunction "C_C") (pintype "passive"))
      (node (ref "Q1") (pin "4") (pinfunction "GND_4") (pintype "power_in"))
      (node (ref "R10") (pin "1") (pinfunction "1_1") (pintype "passive"))
      (node (ref "R11") (pin "1") (pinfunction "1_1") (pintype "passive"))
      (node (ref "R12") (pin "1") (pinfunction "1_1") (pintype "passive"))
      (node (ref "R14") (pin "1") (pinfunction "1_1") (pintype "passive"))
      (node (ref "R15") (pin "1") (pinfunction "1_1") (pintype "passive"))
      (node (ref "R5") (pin "1") (pinfunction "1_1") (pintype "passive"))
      (node (ref "R6") (pin "1") (pinfunction "1_1") (pintype "passive"))
      (node (ref "R9") (pin "1") (pinfunction "1_1") (pintype "passive"))
      (node (ref "S2") (pin "3") (pinfunction "P_3") (pintype "passive"))
      (node (ref "S2") (pin "4") (pinfunction "P1_4") (pintype "passive"))
      (node (ref "SV1") (pin "1") (pinfunction "1_1") (pintype "passive"))
      (node (ref "SV1") (pin "2") (pinfunction "2_2") (pintype "passive"))
      (node (ref "SV1") (pin "20") (pinfunction "20_20") (pintype "passive"))
      (node (ref "SV2") (pin "1") (pinfunction "1_1") (pintype "passive"))
      (node (ref "SV3") (pin "2") (pinfunction "2_2") (pintype "passive"))
      (node (ref "SV3") (pin "4") (pinfunction "4_4") (pintype "passive"))
      (node (ref "SV3") (pin "6") (pinfunction "6_6") (pintype "passive"))
      (node (ref "SV5") (pin "5") (pinfunction "5_5") (pintype "passive"))
      (node (ref "SV5") (pin "7") (pinfunction "7_7") (pintype "passive"))
      (node (ref "SV6") (pin "5") (pinfunction "5_5") (pintype "passive"))
    )
    (net (code "37") (name "Net-(IC6A-O)") (class "Default")
      (node (ref "IC6") (pin "8") (pinfunction "O_8") (pintype "output"))
      (node (ref "IC7") (pin "1") (pinfunction "I_1") (pintype "input"))
    )
    (net (code "38") (name "Net-(IC11-DIS)") (class "Default")
      (node (ref "C19") (pin "1") (pinfunction "1_1") (pintype "passive"))
      (node (ref "IC11") (pin "6") (pinfunction "TRE_6") (pintype "input"))
      (node (ref "IC11") (pin "7") (pinfunction "DIS_7") (pintype "input"))
      (node (ref "R18") (pin "2") (pinfunction "2_2") (pintype "passive"))
    )
    (net (code "39") (name "Net-(IC11-TRI)") (class "Default")
      (node (ref "C18") (pin "1") (pinfunction "1_1") (pintype "passive"))
      (node (ref "IC11") (pin "2") (pinfunction "TRI_2") (pintype "input"))
      (node (ref "R16") (pin "2") (pinfunction "2_2") (pintype "passive"))
      (node (ref "S2") (pin "1") (pinfunction "S_1") (pintype "passive"))
      (node (ref "S2") (pin "2") (pinfunction "S1_2") (pintype "passive"))
    )
    (net (code "40") (name "Net-(IC12A-I1)") (class "Default")
      (node (ref "IC12") (pin "2") (pinfunction "I1_2") (pintype "input"))
      (node (ref "IC12") (pin "6") (pinfunction "O_6") (pintype "output"))
    )
    (net (code "41") (name "Net-(IC12A-O)") (class "Default")
      (node (ref "IC12") (pin "3") (pinfunction "O_3") (pintype "output"))
      (node (ref "IC7") (pin "5") (pinfunction "I_5") (pintype "input"))
    )
    (net (code "42") (name "Net-(LED1-PadA)") (class "Default")
      (node (ref "LED1") (pin "A") (pinfunction "A_A") (pintype "passive"))
      (node (ref "R19") (pin "2") (pinfunction "2_2") (pintype "passive"))
    )
    (net (code "43") (name "Net-(LED2-PadA)") (class "Default")
      (node (ref "LED2") (pin "A") (pinfunction "A_A") (pintype "passive"))
      (node (ref "R20") (pin "2") (pinfunction "2_2") (pintype "passive"))
    )
    (net (code "44") (name "Net-(LED3-PadA)") (class "Default")
      (node (ref "LED3") (pin "A") (pinfunction "A_A") (pintype "passive"))
      (node (ref "R7") (pin "2") (pinfunction "2_2") (pintype "passive"))
    )
    (net (code "45") (name "Net-(LED4-PadA)") (class "Default")
      (node (ref "LED4") (pin "A") (pinfunction "A_A") (pintype "passive"))
      (node (ref "R8") (pin "2") (pinfunction "2_2") (pintype "passive"))
    )
    (net (code "46") (name "Net-(LED5-PadA)") (class "Default")
      (node (ref "LED5") (pin "A") (pinfunction "A_A") (pintype "passive"))
      (node (ref "R13") (pin "2") (pinfunction "2_2") (pintype "passive"))
    )
    (net (code "47") (name "Net-(LED6-PadA)") (class "Default")
      (node (ref "LED6") (pin "A") (pinfunction "A_A") (pintype "passive"))
      (node (ref "R21") (pin "2") (pinfunction "2_2") (pintype "passive"))
    )
    (net (code "48") (name "OUT0") (class "Default")
      (node (ref "IC5") (pin "15") (pinfunction "OP3_15") (pintype "output"))
      (node (ref "SV6") (pin "8") (pinfunction "8_8") (pintype "passive"))
    )
    (net (code "49") (name "OUT1") (class "Default")
      (node (ref "IC5") (pin "14") (pinfunction "OP1_14") (pintype "output"))
      (node (ref "SV6") (pin "7") (pinfunction "7_7") (pintype "passive"))
    )
    (net (code "50") (name "RESET") (class "Default")
      (node (ref "IC11") (pin "3") (pinfunction "OUT_3") (pintype "output"))
      (node (ref "IC13") (pin "1") (pinfunction "I_1") (pintype "input"))
      (node (ref "IC13") (pin "3") (pinfunction "I_3") (pintype "input"))
    )
    (net (code "51") (name "R{slash}~{W}") (class "Default")
      (node (ref "IC1") (pin "30") (pinfunction "R/~{W}_30") (pintype "output"))
      (node (ref "IC2") (pin "29") (pinfunction "~{WE}_29") (pintype "input"))
      (node (ref "IC3") (pin "31") (pinfunction "~{WE}_31") (pintype "input"))
      (node (ref "IC4") (pin "27") (pinfunction "~{WE}_27") (pintype "input"))
      (node (ref "IC5") (pin "9") (pinfunction "R/~{W}_9") (pintype "input"))
      (node (ref "IC7") (pin "3") (pinfunction "I_3") (pintype "input"))
      (node (ref "SV1") (pin "13") (pinfunction "13_13") (pintype "passive"))
    )
    (net (code "52") (name "STATUS0") (class "Default")
      (node (ref "IC5") (pin "17") (pinfunction "OP7_17") (pintype "output"))
      (node (ref "R8") (pin "1") (pinfunction "1_1") (pintype "passive"))
    )
    (net (code "53") (name "STATUS1") (class "Default")
      (node (ref "IC5") (pin "16") (pinfunction "OP5_16") (pintype "output"))
      (node (ref "R7") (pin "1") (pinfunction "1_1") (pintype "passive"))
    )
    (net (code "54") (name "SW0") (class "Default")
      (node (ref "IC5") (pin "5") (pinfunction "IP1_5") (pintype "input"))
      (node (ref "SV6") (pin "1") (pinfunction "1_1") (pintype "passive"))
    )
    (net (code "55") (name "SW1") (class "Default")
      (node (ref "IC5") (pin "8") (pinfunction "IP0_8") (pintype "input"))
      (node (ref "SV6") (pin "2") (pinfunction "2_2") (pintype "passive"))
    )
    (net (code "56") (name "SW2") (class "Default")
      (node (ref "IC5") (pin "40") (pinfunction "IP2_40") (pintype "input"))
      (node (ref "SV6") (pin "3") (pinfunction "3_3") (pintype "passive"))
    )
    (net (code "57") (name "UART0_RX") (class "Default")
      (node (ref "IC5") (pin "35") (pinfunction "RXDA_35") (pintype "input"))
      (node (ref "SV5") (pin "4") (pinfunction "4_4") (pintype "passive"))
    )
    (net (code "58") (name "UART0_TX") (class "Default")
      (node (ref "IC5") (pin "33") (pinfunction "TXDA_33") (pintype "output"))
      (node (ref "SV5") (pin "3") (pinfunction "3_3") (pintype "passive"))
    )
    (net (code "59") (name "UART1_RX") (class "Default")
      (node (ref "IC5") (pin "11") (pinfunction "RXDB_11") (pintype "output"))
      (node (ref "SV5") (pin "2") (pinfunction "2_2") (pintype "passive"))
    )
    (net (code "60") (name "UART1_TX") (class "Default")
      (node (ref "IC5") (pin "13") (pinfunction "TXDB_13") (pintype "bidirectional"))
      (node (ref "SV5") (pin "1") (pinfunction "1_1") (pintype "passive"))
    )
    (net (code "61") (name "VFD_BUSY") (class "Default")
      (node (ref "IC5") (pin "3") (pinfunction "IP3_3") (pintype "input"))
      (node (ref "SV2") (pin "3") (pinfunction "3_3") (pintype "passive"))
    )
    (net (code "62") (name "unconnected-(IC1-A19-Pad19)") (class "Default")
      (node (ref "IC1") (pin "19") (pinfunction "A19_19") (pintype "output"))
    )
    (net (code "63") (name "unconnected-(IC1-BG-Pad32)") (class "Default")
      (node (ref "IC1") (pin "32") (pinfunction "BG_32") (pintype "output"))
    )
    (net (code "64") (name "unconnected-(IC1-DS-Pad29)") (class "Default")
      (node (ref "IC1") (pin "29") (pinfunction "DS_29") (pintype "output"))
    )
    (net (code "65") (name "unconnected-(IC1-E-Pad38)") (class "Default")
      (node (ref "IC1") (pin "38") (pinfunction "E_38") (pintype "output"))
    )
    (net (code "66") (name "unconnected-(IC5-IP4-Pad43)") (class "Default")
      (node (ref "IC5") (pin "43") (pinfunction "IP4_43") (pintype "input"))
    )
    (net (code "67") (name "unconnected-(IC5-IP5-Pad42)") (class "Default")
      (node (ref "IC5") (pin "42") (pinfunction "IP5_42") (pintype "input"))
    )
    (net (code "68") (name "unconnected-(IC5-OP0-Pad32)") (class "Default")
      (node (ref "IC5") (pin "32") (pinfunction "OP0_32") (pintype "output"))
    )
    (net (code "69") (name "unconnected-(IC5-OP2-Pad31)") (class "Default")
      (node (ref "IC5") (pin "31") (pinfunction "OP2_31") (pintype "output"))
    )
    (net (code "70") (name "unconnected-(IC5-OP6-Pad29)") (class "Default")
      (node (ref "IC5") (pin "29") (pinfunction "OP6_29") (pintype "output"))
    )
    (net (code "71") (name "unconnected-(IC5-X2-Pad37)") (class "Default")
      (node (ref "IC5") (pin "37") (pinfunction "X2_37") (pintype "output"))
    )
    (net (code "72") (name "unconnected-(IC7D-O-Pad8)") (class "Default")
      (node (ref "IC7") (pin "8") (pinfunction "O_8") (pintype "output"))
    )
    (net (code "73") (name "unconnected-(IC7E-O-Pad10)") (class "Default")
      (node (ref "IC7") (pin "10") (pinfunction "O_10") (pintype "output"))
    )
    (net (code "74") (name "unconnected-(IC7F-O-Pad12)") (class "Default")
      (node (ref "IC7") (pin "12") (pinfunction "O_12") (pintype "output"))
    )
    (net (code "75") (name "unconnected-(IC9C-O-Pad10)") (class "Default")
      (node (ref "IC9") (pin "10") (pinfunction "O_10") (pintype "open_collector"))
    )
    (net (code "76") (name "unconnected-(IC9D-O-Pad11)") (class "Default")
      (node (ref "IC9") (pin "11") (pinfunction "O_11") (pintype "open_collector"))
    )
    (net (code "77") (name "unconnected-(IC12C-O-Pad8)") (class "Default")
      (node (ref "IC12") (pin "8") (pinfunction "O_8") (pintype "output"))
    )
    (net (code "78") (name "unconnected-(IC12D-O-Pad11)") (class "Default")
      (node (ref "IC12") (pin "11") (pinfunction "O_11") (pintype "output"))
    )
    (net (code "79") (name "unconnected-(IC13C-O-Pad6)") (class "Default")
      (node (ref "IC13") (pin "6") (pinfunction "O_6") (pintype "open_collector"))
    )
    (net (code "80") (name "unconnected-(IC13D-O-Pad8)") (class "Default")
      (node (ref "IC13") (pin "8") (pinfunction "O_8") (pintype "open_collector"))
    )
    (net (code "81") (name "unconnected-(IC13E-O-Pad10)") (class "Default")
      (node (ref "IC13") (pin "10") (pinfunction "O_10") (pintype "open_collector"))
    )
    (net (code "82") (name "unconnected-(IC13F-O-Pad12)") (class "Default")
      (node (ref "IC13") (pin "12") (pinfunction "O_12") (pintype "open_collector"))
    )
    (net (code "83") (name "unconnected-(Q1-TS-Pad1)") (class "Default")
      (node (ref "Q1") (pin "1") (pinfunction "TS_1") (pintype "passive"))
    )
    (net (code "84") (name "unconnected-(SV1-Pad15)") (class "Default")
      (node (ref "SV1") (pin "15") (pinfunction "15_15") (pintype "passive"))
    )
    (net (code "85") (name "unconnected-(SV2-Pad6)") (class "Default")
      (node (ref "SV2") (pin "6") (pinfunction "6_6") (pintype "passive"))
    )
    (net (code "86") (name "unconnected-(SV6-Pad4)") (class "Default")
      (node (ref "SV6") (pin "4") (pinfunction "4_4") (pintype "passive"))
    )
    (net (code "87") (name "unconnected-(SV6-Pad9)") (class "Default")
      (node (ref "SV6") (pin "9") (pinfunction "9_9") (pintype "passive"))
    )
    (net (code "88") (name "unconnected-(SV6-Pad10)") (class "Default")
      (node (ref "SV6") (pin "10") (pinfunction "10_10") (pintype "passive"))
    )
    (net (code "89") (name "~{68681_CS}") (class "Default")
      (node (ref "IC5") (pin "39") (pinfunction "~{CS}_39") (pintype "input"))
      (node (ref "IC8") (pin "13") (pinfunction "Y2_13") (pintype "output"))
    )
    (net (code "90") (name "~{68681_DTACK}") (class "Default")
      (node (ref "IC5") (pin "10") (pinfunction "~{DTACK}_10") (pintype "output"))
      (node (ref "IC6") (pin "12") (pinfunction "I7_12") (pintype "input"))
      (node (ref "R1") (pin "1") (pinfunction "1_1") (pintype "passive"))
    )
    (net (code "91") (name "~{68681_IACK}") (class "Default")
      (node (ref "IC5") (pin "41") (pinfunction "~{IACK}_41") (pintype "input"))
      (node (ref "IC7") (pin "6") (pinfunction "O_6") (pintype "output"))
    )
    (net (code "92") (name "~{AS}") (class "Default")
      (node (ref "IC1") (pin "28") (pinfunction "AS_28") (pintype "output"))
      (node (ref "IC8") (pin "5") (pinfunction "G2B_5") (pintype "input"))
    )
    (net (code "93") (name "~{DTACK}") (class "Default")
      (node (ref "IC1") (pin "31") (pinfunction "DTACK_31") (pintype "input"))
      (node (ref "IC7") (pin "2") (pinfunction "O_2") (pintype "output"))
      (node (ref "LED6") (pin "C") (pinfunction "C_C") (pintype "passive"))
    )
    (net (code "94") (name "~{HALT}") (class "Default")
      (node (ref "IC1") (pin "36") (pinfunction "HALT_36") (pintype "bidirectional"))
      (node (ref "IC13") (pin "4") (pinfunction "O_4") (pintype "open_collector"))
      (node (ref "LED2") (pin "C") (pinfunction "C_C") (pintype "passive"))
      (node (ref "R17") (pin "1") (pinfunction "1_1") (pintype "passive"))
    )
    (net (code "95") (name "~{IPL1}") (class "Default")
      (node (ref "IC1") (pin "41") (pinfunction "IPL1_41") (pintype "input"))
      (node (ref "IC5") (pin "24") (pinfunction "~{INTR}_24") (pintype "output"))
    )
    (net (code "96") (name "~{NIXIE_CS}") (class "Default")
      (node (ref "IC6") (pin "6") (pinfunction "I5_6") (pintype "input"))
      (node (ref "IC8") (pin "11") (pinfunction "Y4_11") (pintype "output"))
      (node (ref "SV1") (pin "17") (pinfunction "17_17") (pintype "passive"))
    )
    (net (code "97") (name "~{OE}") (class "Default")
      (node (ref "IC2") (pin "24") (pinfunction "~{OE}_24") (pintype "input"))
      (node (ref "IC3") (pin "24") (pinfunction "~{OE}_24") (pintype "input"))
      (node (ref "IC4") (pin "22") (pinfunction "~{OE}_22") (pintype "input"))
      (node (ref "IC7") (pin "4") (pinfunction "O_4") (pintype "output"))
    )
    (net (code "98") (name "~{RAM_CS0}") (class "Default")
      (node (ref "IC8") (pin "9") (pinfunction "Y6_9") (pintype "output"))
      (node (ref "IC9") (pin "6") (pinfunction "I1_6") (pintype "input"))
    )
    (net (code "99") (name "~{RAM_CS1}") (class "Default")
      (node (ref "IC8") (pin "7") (pinfunction "Y7_7") (pintype "output"))
      (node (ref "IC9") (pin "5") (pinfunction "I0_5") (pintype "input"))
    )
    (net (code "100") (name "~{RAM_CS}") (class "Default")
      (node (ref "IC2") (pin "22") (pinfunction "~{CE1}_22") (pintype "input"))
      (node (ref "IC6") (pin "4") (pinfunction "I3_4") (pintype "input"))
      (node (ref "IC9") (pin "4") (pinfunction "O_4") (pintype "open_collector"))
      (node (ref "R3") (pin "1") (pinfunction "1_1") (pintype "passive"))
    )
    (net (code "101") (name "~{RESET}") (class "Default")
      (node (ref "IC1") (pin "37") (pinfunction "RESET_37") (pintype "bidirectional"))
      (node (ref "IC13") (pin "2") (pinfunction "O_2") (pintype "open_collector"))
      (node (ref "IC5") (pin "38") (pinfunction "~{RESET}_38") (pintype "input"))
      (node (ref "LED1") (pin "C") (pinfunction "C_C") (pintype "passive"))
      (node (ref "R4") (pin "1") (pinfunction "1_1") (pintype "passive"))
    )
    (net (code "102") (name "~{ROM_CS0}") (class "Default")
      (node (ref "IC8") (pin "15") (pinfunction "Y0_15") (pintype "output"))
      (node (ref "IC9") (pin "1") (pinfunction "I0_1") (pintype "input"))
    )
    (net (code "103") (name "~{ROM_CS1}") (class "Default")
      (node (ref "IC8") (pin "14") (pinfunction "Y1_14") (pintype "output"))
      (node (ref "IC9") (pin "2") (pinfunction "I1_2") (pintype "input"))
    )
    (net (code "104") (name "~{ROM_CS}") (class "Default")
      (node (ref "IC3") (pin "22") (pinfunction "~{CS}_22") (pintype "input"))
      (node (ref "IC6") (pin "3") (pinfunction "I2_3") (pintype "input"))
      (node (ref "IC9") (pin "3") (pinfunction "O_3") (pintype "open_collector"))
      (node (ref "R2") (pin "1") (pinfunction "1_1") (pintype "passive"))
    )
    (net (code "105") (name "~{RTC_CS}") (class "Default")
      (node (ref "IC4") (pin "20") (pinfunction "~{CS}_20") (pintype "input"))
      (node (ref "IC6") (pin "5") (pinfunction "I4_5") (pintype "input"))
      (node (ref "IC8") (pin "12") (pinfunction "Y3_12") (pintype "output"))
    )
    (net (code "106") (name "~{VFD_CS}") (class "Default")
      (node (ref "IC6") (pin "11") (pinfunction "I6_11") (pintype "input"))
      (node (ref "IC8") (pin "10") (pinfunction "Y5_10") (pintype "output"))
      (node (ref "SV2") (pin "5") (pinfunction "5_5") (pintype "passive"))
    )
    (net (code "107") (name "~{VFD_RESET}") (class "Default")
      (node (ref "IC5") (pin "30") (pinfunction "OP4_30") (pintype "output"))
      (node (ref "SV2") (pin "4") (pinfunction "4_4") (pintype "passive"))
    )
  )
)
